# motor.net
KiCad netlist of a schematic drawn in EAGLE
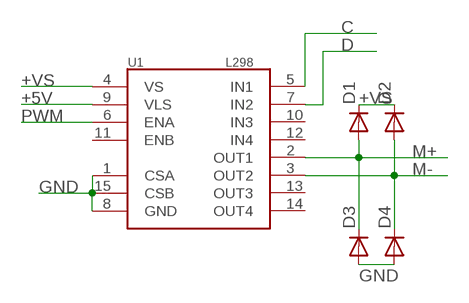
[diagram p0: schematic, sheet 1]

(export (version "E")
  (design (tool "Eeschema 10.0.6"))
  (components
    (comp (ref "D1")
      (value "DIODEPTH")
      (footprint "eagle-import:DIODE-1N4001")
      (libsource (lib "eagle-import") (part "DIODEPTH"))
    )
    (comp (ref "D2")
      (value "DIODEPTH")
      (footprint "eagle-import:DIODE-1N4001")
      (libsource (lib "eagle-import") (part "DIODEPTH"))
    )
    (comp (ref "D3")
      (value "DIODEPTH")
      (footprint "eagle-import:DIODE-1N4001")
      (libsource (lib "eagle-import") (part "DIODEPTH"))
    )
    (comp (ref "D4")
      (value "DIODEPTH")
      (footprint "eagle-import:DIODE-1N4001")
      (libsource (lib "eagle-import") (part "DIODEPTH"))
    )
    (comp (ref "U1")
      (value "L298")
      (footprint "eagle-import:MULTIWATT15")
      (libsource (lib "eagle-import") (part "L298"))
    )
  )
  (nets
    (net (code "1") (name "/+5V") (class "Default")
      (node (ref "U1") (pin "9") (pinfunction "VLS_9") (pintype "bidirectional"))
    )
    (net (code "2") (name "/+VS") (class "Default")
      (node (ref "D1") (pin "C") (pinfunction "C_C") (pintype "passive"))
      (node (ref "D2") (pin "C") (pinfunction "C_C") (pintype "passive"))
      (node (ref "U1") (pin "4") (pinfunction "VS_4") (pintype "bidirectional"))
    )
    (net (code "3") (name "/C") (class "Default")
      (node (ref "U1") (pin "5") (pinfunction "IN1_5") (pintype "bidirectional"))
    )
    (net (code "4") (name "/D") (class "Default")
      (node (ref "U1") (pin "7") (pinfunction "IN2_7") (pintype "bidirectional"))
    )
    (net (code "5") (name "/GND") (class "Default")
      (node (ref "D3") (pin "A") (pinfunction "A_A") (pintype "passive"))
      (node (ref "D4") (pin "A") (pinfunction "A_A") (pintype "passive"))
      (node (ref "U1") (pin "1") (pinfunction "CSA_1") (pintype "bidirectional"))
      (node (ref "U1") (pin "15") (pinfunction "CSB_15") (pintype "bidirectional"))
      (node (ref "U1") (pin "8") (pinfunction "GND_8") (pintype "bidirectional"))
    )
    (net (code "6") (name "/M+") (class "Default")
      (node (ref "D1") (pin "A") (pinfunction "A_A") (pintype "passive"))
      (node (ref "D3") (pin "C") (pinfunction "C_C") (pintype "passive"))
      (node (ref "U1") (pin "2") (pinfunction "OUT1_2") (pintype "bidirectional"))
    )
    (net (code "7") (name "/M-") (class "Default")
      (node (ref "D2") (pin "A") (pinfunction "A_A") (pintype "passive"))
      (node (ref "D4") (pin "C") (pinfunction "C_C") (pintype "passive"))
      (node (ref "U1") (pin "3") (pinfunction "OUT2_3") (pintype "bidirectional"))
    )
    (net (code "8") (name "/PWM") (class "Default")
      (node (ref "U1") (pin "6") (pinfunction "ENA_6") (pintype "bidirectional"))
    )
    (net (code "9") (name "unconnected-(U1-ENB-Pad11)") (class "Default")
      (node (ref "U1") (pin "11") (pinfunction "ENB_11") (pintype "bidirectional"))
    )
    (net (code "10") (name "unconnected-(U1-IN3-Pad10)") (class "Default")
      (node (ref "U1") (pin "10") (pinfunction "IN3_10") (pintype "bidirectional"))
    )
    (net (code "11") (name "unconnected-(U1-IN4-Pad12)") (class "Default")
      (node (ref "U1") (pin "12") (pinfunction "IN4_12") (pintype "bidirectional"))
    )
    (net (code "12") (name "unconnected-(U1-OUT3-Pad13)") (class "Default")
      (node (ref "U1") (pin "13") (pinfunction "OUT3_13") (pintype "bidirectional"))
    )
    (net (code "13") (name "unconnected-(U1-OUT4-Pad14)") (class "Default")
      (node (ref "U1") (pin "14") (pinfunction "OUT4_14") (pintype "bidirectional"))
    )
  )
)
